# ProPrj___2025-07-18.net
KiCad netlist of a schematic drawn in EasyEDA Pro
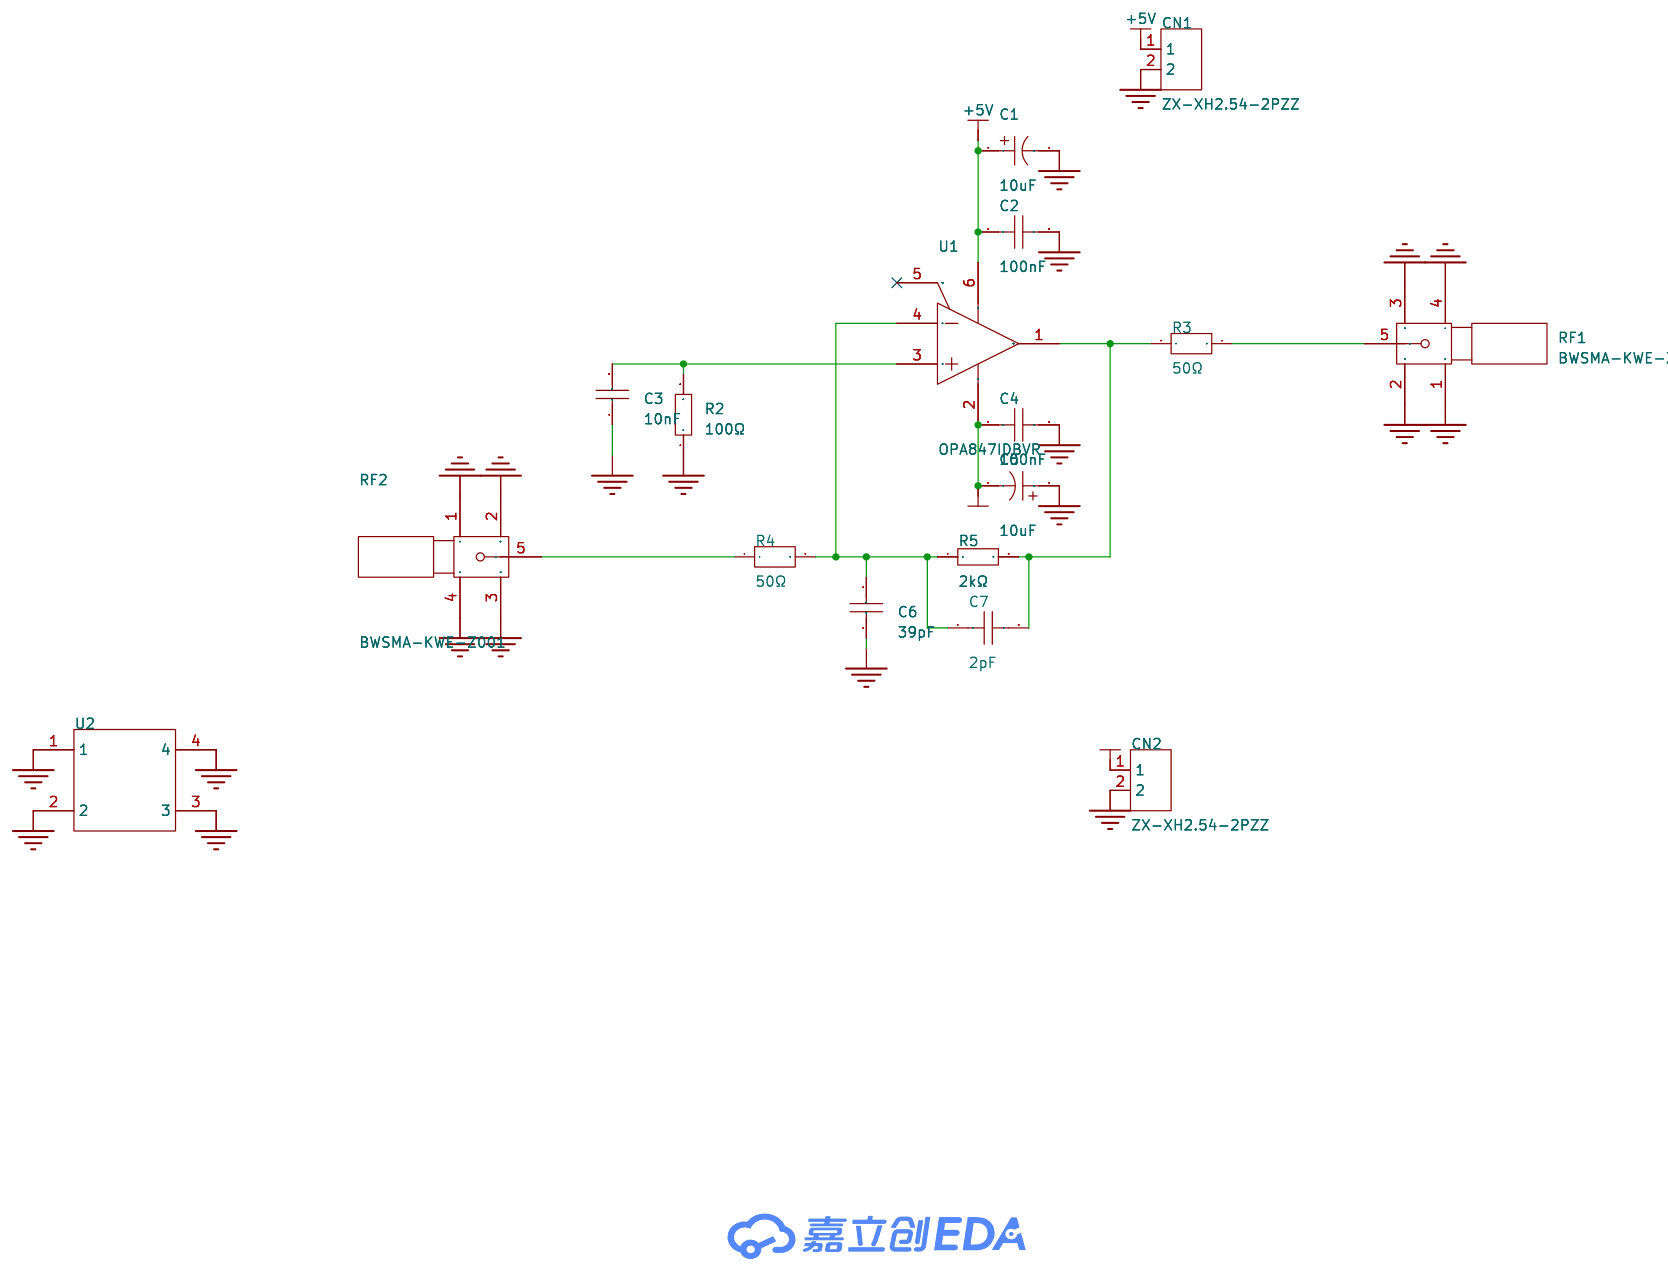
[diagram p0: schematic sheet]

(export (version "E")
  (design (tool "Eeschema 10.0.6"))
  (components
    (comp (ref "C1")
      (value "10uF")
      (footprint "easyedapro:CAP-SMD_BD5.0-L5.3-W5.3-LS6.0-FD")
      (description "容值:10uF;精度:±20%;额定电压:50V;纹波电流:18mA@120Hz;")
      (fields (field (name "Manufacturer Part") "JVJ50v10M5x5") (field (name "Manufacturer") "捷而瑞"))
      (libsource (lib "easyedapro") (part "JVJ50V10M5X5"))
    )
    (comp (ref "C2")
      (value "100nF")
      (footprint "easyedapro:C0603")
      (description "容值:100nF;精度:±10%;额定电压:50V;温度系数:X7R;")
      (fields
        (field (name "Manufacturer Part") "CC0603KRX7R9BB104")
        (field (name "Manufacturer") "YAGEO(国巨)")
      )
      (libsource (lib "easyedapro") (part "CC0603KRX7R9BB104"))
    )
    (comp (ref "C3")
      (value "10nF")
      (footprint "easyedapro:C0603")
      (description "容值:10nF;精度:±10%;额定电压:50V;温度系数:X7R;")
      (fields (field (name "Manufacturer Part") "0603B103K500NT") (field (name "Manufacturer") "FH(风华)"))
      (libsource (lib "easyedapro") (part "0603B103K500NT"))
    )
    (comp (ref "C4")
      (value "100nF")
      (footprint "easyedapro:C0603")
      (description "容值:100nF;精度:±10%;额定电压:50V;温度系数:X7R;")
      (fields
        (field (name "Manufacturer Part") "CC0603KRX7R9BB104")
        (field (name "Manufacturer") "YAGEO(国巨)")
      )
      (libsource (lib "easyedapro") (part "CC0603KRX7R9BB104"))
    )
    (comp (ref "C5")
      (value "10uF")
      (footprint "easyedapro:CAP-SMD_BD5.0-L5.3-W5.3-LS6.0-FD")
      (description "容值:10uF;精度:±20%;额定电压:50V;纹波电流:18mA@120Hz;")
      (fields (field (name "Manufacturer Part") "JVJ50v10M5x5") (field (name "Manufacturer") "捷而瑞"))
      (libsource (lib "easyedapro") (part "JVJ50V10M5X5"))
    )
    (comp (ref "C6")
      (value "39pF")
      (footprint "easyedapro:C0603")
      (description "容值:39pF;精度:±5%;额定电压:50V;材质(温度系数):NP0;")
      (fields
        (field (name "Manufacturer Part") "CC0603JRNPO9BN390")
        (field (name "Manufacturer") "YAGEO(国巨)")
      )
      (libsource (lib "easyedapro") (part "CC0603JRNPO9BN390"))
    )
    (comp (ref "C7")
      (value "2pF")
      (footprint "easyedapro:C0603")
      (description "容值:2pF;额定电压:50V;温度系数:C0G;")
      (fields
        (field (name "Manufacturer Part") "CGA0603C0G2R0B500JT")
        (field (name "Manufacturer") "HRE(芯声)")
      )
      (libsource (lib "easyedapro") (part "CGA0603C0G2R0B500JT"))
    )
    (comp (ref "CN1")
      (value "ZX-XH2.54-2PZZ")
      (footprint "easyedapro:CONN-TH_2P-P2.50_HX25003-2A")
      (fields (field (name "Manufacturer") "Megastar(兆星)"))
      (libsource (lib "easyedapro") (part "ZX-XH2.54-2PZZ"))
    )
    (comp (ref "CN2")
      (value "ZX-XH2.54-2PZZ")
      (footprint "easyedapro:CONN-TH_2P-P2.50_HX25003-2A")
      (fields (field (name "Manufacturer") "Megastar(兆星)"))
      (libsource (lib "easyedapro") (part "ZX-XH2.54-2PZZ"))
    )
    (comp (ref "R2")
      (value "100Ω")
      (footprint "easyedapro:R0603")
      (description "电阻类型:厚膜电阻;阻值:100Ω;精度:±1%;功率:100mW;最大工作电压:75V;温度系数:±200ppm/°C;")
      (fields
        (field (name "Manufacturer Part") "0603WAF1000T5E")
        (field (name "Manufacturer") "UNI-ROYAL(厚声)")
      )
      (libsource (lib "easyedapro") (part "0603WAF1000T5E"))
    )
    (comp (ref "R3")
      (value "50Ω")
      (footprint "easyedapro:R0603")
      (description "电阻类型:薄膜电阻;阻值:50Ω;精度:±0.1%;功率:100mW;温度系数:±50ppm/°C;")
      (fields (field (name "Manufacturer Part") "RT0603BRE0750RL") (field (name "Manufacturer") "YAGEO(国巨)"))
      (libsource (lib "easyedapro") (part "RT0603BRE0750RL"))
    )
    (comp (ref "R4")
      (value "50Ω")
      (footprint "easyedapro:R0603")
      (description "电阻类型:薄膜电阻;阻值:50Ω;精度:±0.1%;功率:100mW;温度系数:±50ppm/°C;")
      (fields (field (name "Manufacturer Part") "RT0603BRE0750RL") (field (name "Manufacturer") "YAGEO(国巨)"))
      (libsource (lib "easyedapro") (part "RT0603BRE0750RL"))
    )
    (comp (ref "R5")
      (value "2kΩ")
      (footprint "easyedapro:R0603")
      (description "电阻类型:厚膜电阻;阻值:2kΩ;精度:±1%;功率:100mW;最大工作电压:75V;温度系数:±100ppm/°C;")
      (fields
        (field (name "Manufacturer Part") "0603WAF2001T5E")
        (field (name "Manufacturer") "UNI-ROYAL(厚声)")
      )
      (libsource (lib "easyedapro") (part "0603WAF2001T5E"))
    )
    (comp (ref "RF1")
      (value "BWSMA-KWE-Z001")
      (footprint "easyedapro:SMA-TH_BWSMA-KWE-Z001")
      (fields (field (name "Manufacturer") "BAT WIRELESS(蝙蝠无线)"))
      (libsource (lib "easyedapro") (part "BWSMA-KWE-Z001"))
    )
    (comp (ref "RF2")
      (value "BWSMA-KWE-Z001")
      (footprint "easyedapro:SMA-TH_BWSMA-KWE-Z001")
      (fields (field (name "Manufacturer") "BAT WIRELESS(蝙蝠无线)"))
      (libsource (lib "easyedapro") (part "BWSMA-KWE-Z001"))
    )
    (comp (ref "U1")
      (value "OPA847IDBVR")
      (footprint "easyedapro:SOT-23-6_L2.9-W1.6-P0.95-LS2.8-BL")
      (description "放大器数:单路;轨到轨:-;增益带宽积(GBP):3.9GHz;输入失调电压(Vos):500uV;压摆率(SR):950V/us;输入偏置电流(Ib):19uA;")
      (fields (field (name "Manufacturer") "TI(德州仪器)"))
      (libsource (lib "easyedapro") (part "OPA847IDBVR"))
    )
    (comp (ref "U2")
      (value "~")
      (footprint "easyedapro:22x17x6")
      (libsource (lib "easyedapro") (part "22x17x6"))
    )
  )
  (nets
    (net (code "1") (name "+5V") (class "Default")
      (node (ref "C1") (pin "1") (pinfunction "1_1") (pintype "input"))
      (node (ref "C2") (pin "1") (pinfunction "1_1") (pintype "unspecified"))
      (node (ref "CN1") (pin "1") (pinfunction "1_1") (pintype "unspecified"))
      (node (ref "U1") (pin "6") (pinfunction "VS+_6") (pintype "unspecified"))
    )
    (net (code "2") (name "-5V") (class "Default")
      (node (ref "C4") (pin "1") (pinfunction "1_1") (pintype "unspecified"))
      (node (ref "C5") (pin "2") (pinfunction "2_2") (pintype "input"))
      (node (ref "CN2") (pin "1") (pinfunction "1_1") (pintype "unspecified"))
      (node (ref "U1") (pin "2") (pinfunction "VS-_2") (pintype "unspecified"))
    )
    (net (code "3") (name "GND") (class "Default")
      (node (ref "C1") (pin "2") (pinfunction "2_2") (pintype "input"))
      (node (ref "C2") (pin "2") (pinfunction "2_2") (pintype "unspecified"))
      (node (ref "C3") (pin "1") (pinfunction "1_1") (pintype "input"))
      (node (ref "C4") (pin "2") (pinfunction "2_2") (pintype "unspecified"))
      (node (ref "C5") (pin "1") (pinfunction "1_1") (pintype "input"))
      (node (ref "C6") (pin "1") (pinfunction "1_1") (pintype "input"))
      (node (ref "CN1") (pin "2") (pinfunction "2_2") (pintype "unspecified"))
      (node (ref "CN2") (pin "2") (pinfunction "2_2") (pintype "unspecified"))
      (node (ref "R2") (pin "1") (pinfunction "1_1") (pintype "input"))
      (node (ref "RF1") (pin "1") (pinfunction "1_1") (pintype "unspecified"))
      (node (ref "RF1") (pin "2") (pinfunction "2_2") (pintype "unspecified"))
      (node (ref "RF1") (pin "3") (pinfunction "3_3") (pintype "unspecified"))
      (node (ref "RF1") (pin "4") (pinfunction "4_4") (pintype "unspecified"))
      (node (ref "RF2") (pin "1") (pinfunction "1_1") (pintype "unspecified"))
      (node (ref "RF2") (pin "2") (pinfunction "2_2") (pintype "unspecified"))
      (node (ref "RF2") (pin "3") (pinfunction "3_3") (pintype "unspecified"))
      (node (ref "RF2") (pin "4") (pinfunction "4_4") (pintype "unspecified"))
      (node (ref "U2") (pin "1") (pinfunction "1_1") (pintype "input"))
      (node (ref "U2") (pin "2") (pinfunction "2_2") (pintype "input"))
      (node (ref "U2") (pin "3") (pinfunction "3_3") (pintype "input"))
      (node (ref "U2") (pin "4") (pinfunction "4_4") (pintype "input"))
    )
    (net (code "4") (name "Net-(R3-Pad2)") (class "Default")
      (node (ref "R3") (pin "2") (pinfunction "2_2") (pintype "unspecified"))
      (node (ref "RF1") (pin "5") (pinfunction "5_5") (pintype "unspecified"))
    )
    (net (code "5") (name "Net-(R4-Pad1)") (class "Default")
      (node (ref "R4") (pin "1") (pinfunction "1_1") (pintype "unspecified"))
      (node (ref "RF2") (pin "5") (pinfunction "5_5") (pintype "unspecified"))
    )
    (net (code "6") (name "Net-(U1-IN+)") (class "Default")
      (node (ref "C3") (pin "2") (pinfunction "2_2") (pintype "input"))
      (node (ref "R2") (pin "2") (pinfunction "2_2") (pintype "input"))
      (node (ref "U1") (pin "3") (pinfunction "IN+_3") (pintype "unspecified"))
    )
    (net (code "7") (name "Net-(U1-IN-)") (class "Default")
      (node (ref "C6") (pin "2") (pinfunction "2_2") (pintype "input"))
      (node (ref "C7") (pin "1") (pinfunction "1_1") (pintype "unspecified"))
      (node (ref "R4") (pin "2") (pinfunction "2_2") (pintype "unspecified"))
      (node (ref "R5") (pin "1") (pinfunction "1_1") (pintype "input"))
      (node (ref "U1") (pin "4") (pinfunction "IN-_4") (pintype "unspecified"))
    )
    (net (code "8") (name "Net-(U1-OUT)") (class "Default")
      (node (ref "C7") (pin "2") (pinfunction "2_2") (pintype "unspecified"))
      (node (ref "R3") (pin "1") (pinfunction "1_1") (pintype "unspecified"))
      (node (ref "R5") (pin "2") (pinfunction "2_2") (pintype "input"))
      (node (ref "U1") (pin "1") (pinfunction "OUT_1") (pintype "output"))
    )
    (net (code "9") (name "unconnected-(U1-DIS-Pad5)") (class "Default")
      (node (ref "U1") (pin "5") (pinfunction "DIS_5") (pintype "unspecified+no_connect"))
    )
  )
)
